# 7_ICM20948_schdoc.net
KiCad netlist of a schematic drawn in Altium Designer
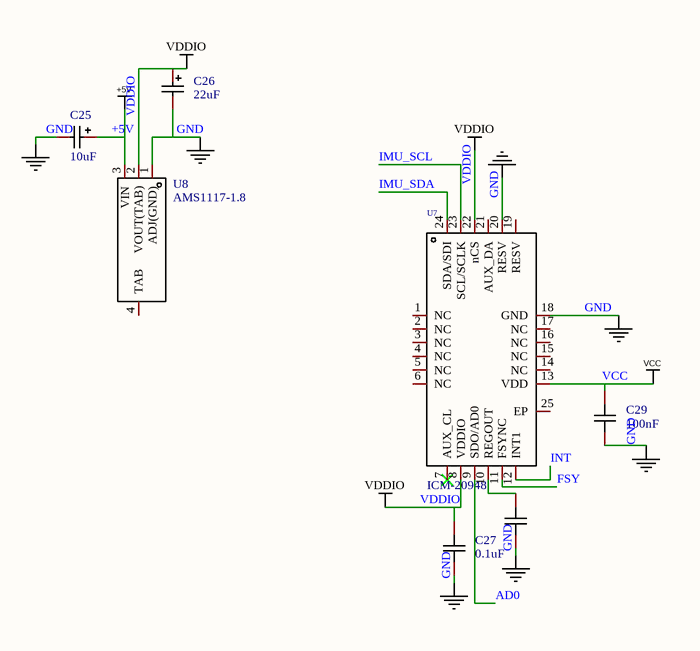
[diagram p0: 7_ICM20948.schdoc.schdoc]

(export (version "E")
  (design (tool "Eeschema 10.0.6"))
  (components
    (comp (ref "C25")
      (value "10uF")
      (description "容值:10uF;精度:±10%;额定电压:16V;等效串联电阻:3Ω@100kHz;")
      (fields
        (field (name "NAME") "10uF")
        (field (name "MANUFACTURER") "Kyocera AVX")
        (field (name "MANUFACTURER PART") "TAJA106K016RNJ")
      )
      (libsource (lib "altium-import") (part "root_0_TAJA106K016RNJ_"))
    )
    (comp (ref "C26")
      (value "22uF")
      (description "容值:22uF;精度:±10%;额定电压:10V;等效串联电阻:3Ω@100kHz;")
      (fields
        (field (name "NAME") "22uF")
        (field (name "MANUFACTURER") "Kyocera AVX")
        (field (name "MANUFACTURER PART") "TAJA226K010RNJ")
      )
      (libsource (lib "altium-import") (part "root_1_TAJA226K010RNJ_"))
    )
    (comp (ref "C27")
      (value "0.1uF")
      (fields (field (name "NAME") "0.1uF"))
      (libsource (lib "altium-import") (part "root_3_CAP_0603_"))
    )
    (comp (ref "C28") (value "0.1uF") (libsource (lib "altium-import") (part "root_3_CAP_0603_")))
    (comp (ref "C29")
      (value "100nF")
      (fields (field (name "NAME") "100nF"))
      (libsource (lib "altium-import") (part "root_3_CAP_0603_"))
    )
    (comp (ref "U7")
      (value "ICM-20948")
      (description "传感器类型:加速度计陀螺仪;")
      (fields (field (name "NAME") "ICM-20948") (field (name "MANUFACTURER") "TDK InvenSense(应美盛)"))
      (libsource (lib "altium-import") (part "root_0_ICM-20948_"))
    )
    (comp (ref "U8")
      (value "AMS1117-1.8")
      (description "输出类型:固定;最大输入电压:18V;输出电压:1.8V;输出电流:1A;电源纹波抑制比(PSRR):60dB@(120Hz);输出极性:正;")
      (fields (field (name "NAME") "AMS1117-1.8") (field (name "MANUFACTURER") "UMW(友台半导体)"))
      (libsource (lib "altium-import") (part "root_3_AMS1117-1.8_C347220_"))
    )
  )
  (nets
    (net (code "1") (name "+5V") (class "Default")
      (node (ref "C25") (pin "1") (pinfunction "1_1") (pintype "passive"))
      (node (ref "U8") (pin "3") (pinfunction "VIN_3") (pintype "passive"))
    )
    (net (code "2") (name "/AD0") (class "Default")
      (node (ref "U7") (pin "9") (pinfunction "SDO/AD0_9") (pintype "passive"))
    )
    (net (code "3") (name "/FSY") (class "Default")
      (node (ref "U7") (pin "11") (pinfunction "FSYNC_11") (pintype "passive"))
    )
    (net (code "4") (name "/GND") (class "Default")
      (node (ref "C25") (pin "2") (pinfunction "2_2") (pintype "passive"))
      (node (ref "C26") (pin "2") (pinfunction "2_2") (pintype "passive"))
      (node (ref "C27") (pin "2") (pinfunction "2_2") (pintype "passive"))
      (node (ref "C28") (pin "2") (pinfunction "2_2") (pintype "passive"))
      (node (ref "C29") (pin "2") (pinfunction "2_2") (pintype "passive"))
      (node (ref "U7") (pin "18") (pinfunction "GND_18") (pintype "passive"))
      (node (ref "U7") (pin "20") (pinfunction "RESV_20") (pintype "passive"))
      (node (ref "U8") (pin "1") (pinfunction "ADJ(GND)_1") (pintype "passive"))
    )
    (net (code "5") (name "/IMU_SCL") (class "Default")
      (node (ref "U7") (pin "23") (pinfunction "SCL/SCLK_23") (pintype "passive"))
    )
    (net (code "6") (name "/IMU_SDA") (class "Default")
      (node (ref "U7") (pin "24") (pinfunction "SDA/SDI_24") (pintype "passive"))
    )
    (net (code "7") (name "/INT") (class "Default")
      (node (ref "U7") (pin "12") (pinfunction "INT1_12") (pintype "passive"))
    )
    (net (code "8") (name "Net-(U7-REGOUT)") (class "Default")
      (node (ref "C28") (pin "1") (pinfunction "1_1") (pintype "passive"))
      (node (ref "U7") (pin "10") (pinfunction "REGOUT_10") (pintype "passive"))
    )
    (net (code "9") (name "VCC") (class "Default")
      (node (ref "C29") (pin "1") (pinfunction "1_1") (pintype "passive"))
      (node (ref "U7") (pin "13") (pinfunction "VDD_13") (pintype "passive"))
    )
    (net (code "10") (name "VDDIO") (class "Default")
      (node (ref "C26") (pin "1") (pinfunction "1_1") (pintype "passive"))
      (node (ref "C27") (pin "1") (pinfunction "1_1") (pintype "passive"))
      (node (ref "U7") (pin "22") (pinfunction "nCS_22") (pintype "passive"))
      (node (ref "U7") (pin "8") (pinfunction "VDDIO_8") (pintype "passive"))
      (node (ref "U8") (pin "2") (pinfunction "VOUT(TAB)_2") (pintype "passive"))
    )
    (net (code "11") (name "unconnected-(U7-AUX_CL-Pad7)") (class "Default")
      (node (ref "U7") (pin "7") (pinfunction "AUX_CL_7") (pintype "passive+no_connect"))
    )
    (net (code "12") (name "unconnected-(U7-AUX_DA-Pad21)") (class "Default")
      (node (ref "U7") (pin "21") (pinfunction "AUX_DA_21") (pintype "passive"))
    )
    (net (code "13") (name "unconnected-(U7-EP-Pad25)") (class "Default")
      (node (ref "U7") (pin "25") (pinfunction "EP_25") (pintype "passive"))
    )
    (net (code "14") (name "unconnected-(U7-NC-Pad1)") (class "Default")
      (node (ref "U7") (pin "1") (pinfunction "NC_1") (pintype "passive"))
    )
    (net (code "15") (name "unconnected-(U7-NC-Pad2)") (class "Default")
      (node (ref "U7") (pin "2") (pinfunction "NC_2") (pintype "passive"))
    )
    (net (code "16") (name "unconnected-(U7-NC-Pad3)") (class "Default")
      (node (ref "U7") (pin "3") (pinfunction "NC_3") (pintype "passive"))
    )
    (net (code "17") (name "unconnected-(U7-NC-Pad4)") (class "Default")
      (node (ref "U7") (pin "4") (pinfunction "NC_4") (pintype "passive"))
    )
    (net (code "18") (name "unconnected-(U7-NC-Pad5)") (class "Default")
      (node (ref "U7") (pin "5") (pinfunction "NC_5") (pintype "passive"))
    )
    (net (code "19") (name "unconnected-(U7-NC-Pad6)") (class "Default")
      (node (ref "U7") (pin "6") (pinfunction "NC_6") (pintype "passive"))
    )
    (net (code "20") (name "unconnected-(U7-NC-Pad14)") (class "Default")
      (node (ref "U7") (pin "14") (pinfunction "NC_14") (pintype "passive"))
    )
    (net (code "21") (name "unconnected-(U7-NC-Pad15)") (class "Default")
      (node (ref "U7") (pin "15") (pinfunction "NC_15") (pintype "passive"))
    )
    (net (code "22") (name "unconnected-(U7-NC-Pad16)") (class "Default")
      (node (ref "U7") (pin "16") (pinfunction "NC_16") (pintype "passive"))
    )
    (net (code "23") (name "unconnected-(U7-NC-Pad17)") (class "Default")
      (node (ref "U7") (pin "17") (pinfunction "NC_17") (pintype "passive"))
    )
    (net (code "24") (name "unconnected-(U7-RESV-Pad19)") (class "Default")
      (node (ref "U7") (pin "19") (pinfunction "RESV_19") (pintype "passive"))
    )
    (net (code "25") (name "unconnected-(U8-TAB-Pad4)") (class "Default")
      (node (ref "U8") (pin "4") (pinfunction "TAB_4") (pintype "passive"))
    )
  )
)
